# B312B.net
KiCad netlist of a schematic drawn in EAGLE
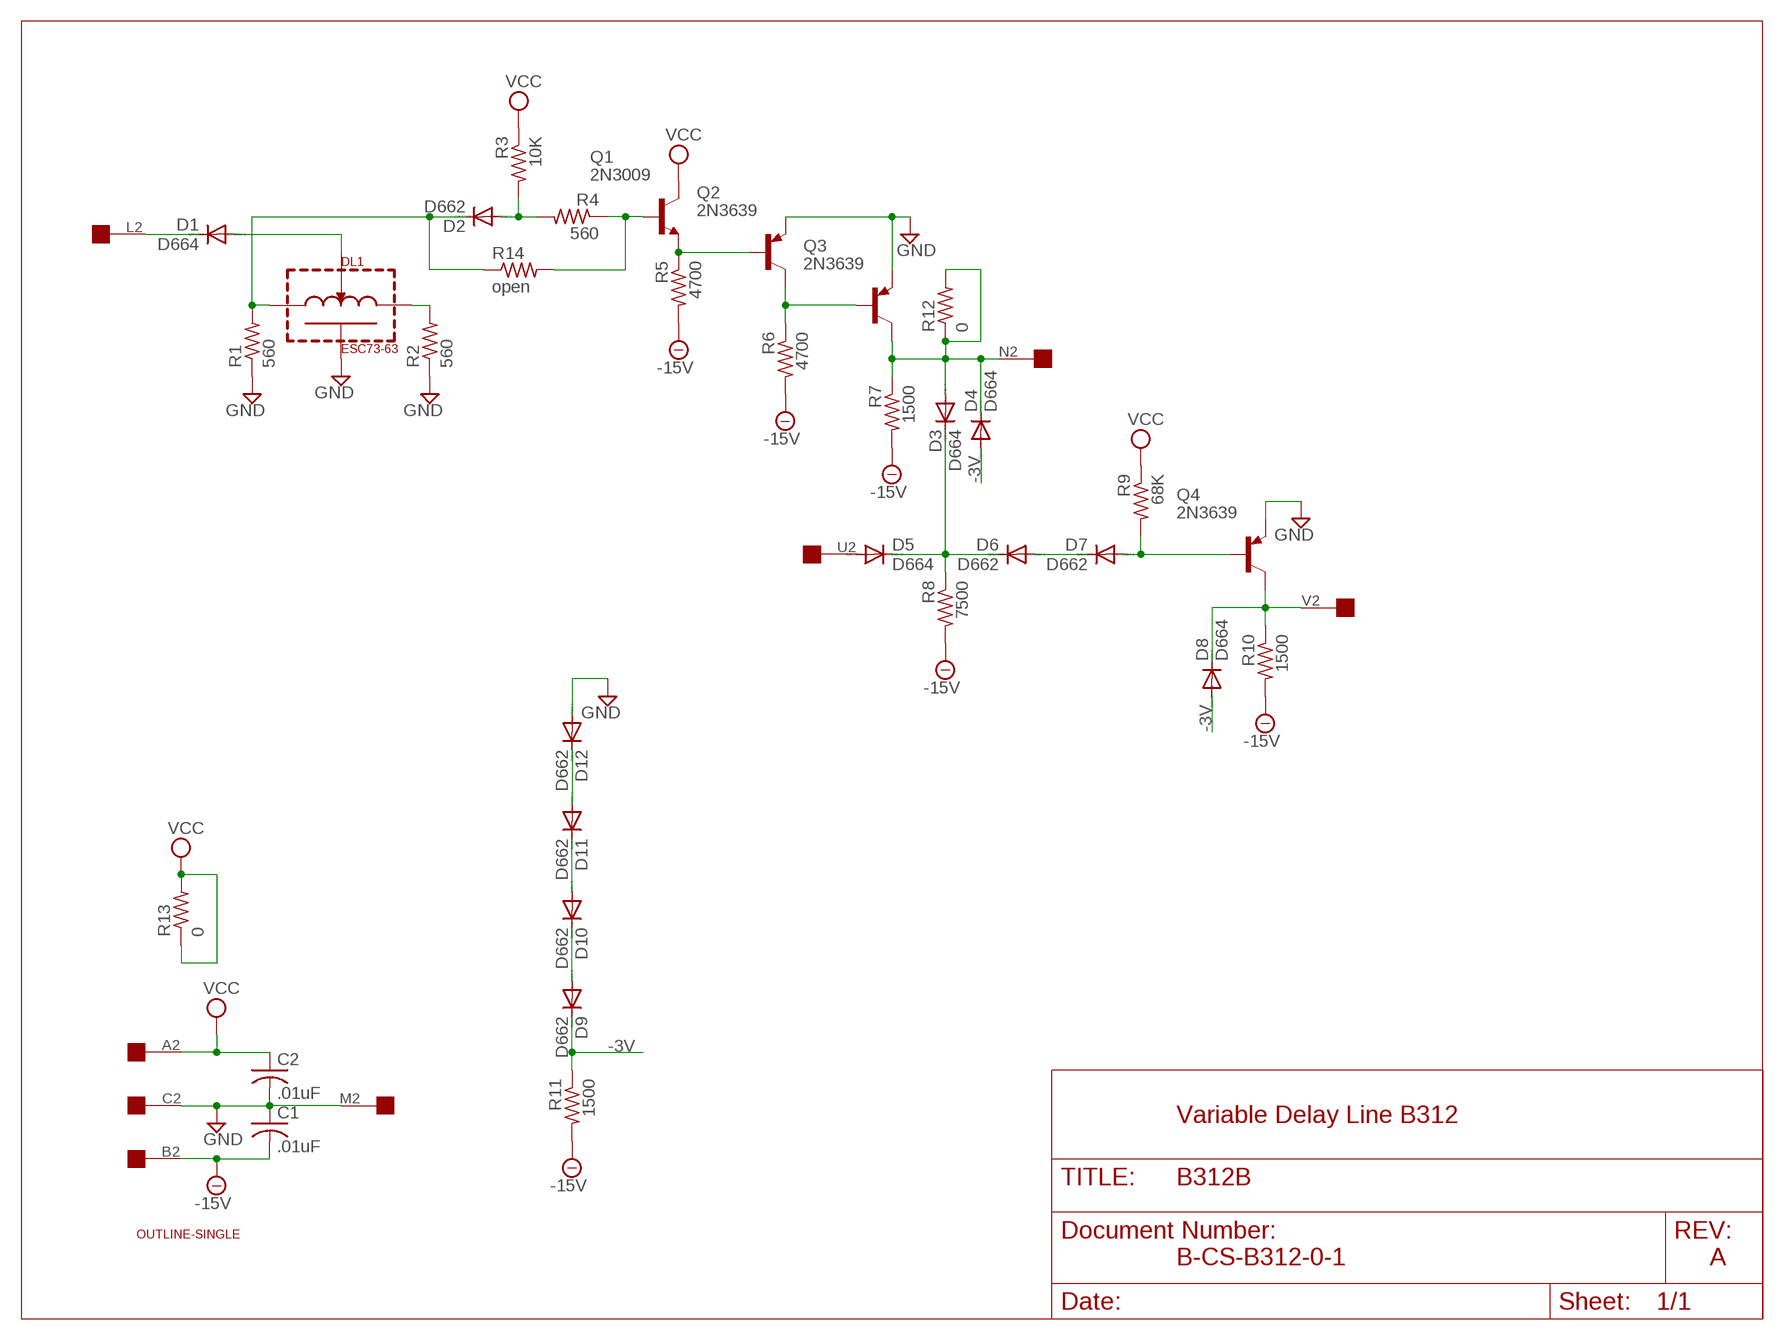
[diagram p0: schematic, sheet 1]

(export (version "E")
  (design (tool "Eeschema 10.0.6"))
  (components
    (comp (ref "C1")
      (value ".01uF")
      (footprint "eagle-import:C063-025X075")
      (libsource (lib "eagle-import") (part "C-US"))
    )
    (comp (ref "C2")
      (value ".01uF")
      (footprint "eagle-import:C063-025X075")
      (libsource (lib "eagle-import") (part "C-US"))
    )
    (comp (ref "D1")
      (value "D664")
      (footprint "eagle-import:DO35-10")
      (libsource (lib "eagle-import") (part "DIODE-DO35-10"))
    )
    (comp (ref "D2")
      (value "D662")
      (footprint "eagle-import:DO35-10")
      (libsource (lib "eagle-import") (part "DIODE-DO35-10"))
    )
    (comp (ref "D3")
      (value "D664")
      (footprint "eagle-import:DO35-10")
      (libsource (lib "eagle-import") (part "DIODE-DO35-10"))
    )
    (comp (ref "D4")
      (value "D664")
      (footprint "eagle-import:DO35-10")
      (libsource (lib "eagle-import") (part "DIODE-DO35-10"))
    )
    (comp (ref "D5")
      (value "D664")
      (footprint "eagle-import:DO35-10")
      (libsource (lib "eagle-import") (part "DIODE-DO35-10"))
    )
    (comp (ref "D6")
      (value "D662")
      (footprint "eagle-import:DO35-10")
      (libsource (lib "eagle-import") (part "DIODE-DO35-10"))
    )
    (comp (ref "D7")
      (value "D662")
      (footprint "eagle-import:DO35-10")
      (libsource (lib "eagle-import") (part "DIODE-DO35-10"))
    )
    (comp (ref "D8")
      (value "D664")
      (footprint "eagle-import:DO35-10")
      (libsource (lib "eagle-import") (part "DIODE-DO35-10"))
    )
    (comp (ref "D9")
      (value "D662")
      (footprint "eagle-import:DO35-10")
      (libsource (lib "eagle-import") (part "DIODE-DO35-10"))
    )
    (comp (ref "D10")
      (value "D662")
      (footprint "eagle-import:DO35-10")
      (libsource (lib "eagle-import") (part "DIODE-DO35-10"))
    )
    (comp (ref "D11")
      (value "D662")
      (footprint "eagle-import:DO35-10")
      (libsource (lib "eagle-import") (part "DIODE-DO35-10"))
    )
    (comp (ref "D12")
      (value "D662")
      (footprint "eagle-import:DO35-10")
      (libsource (lib "eagle-import") (part "DIODE-DO35-10"))
    )
    (comp (ref "DL1")
      (value "ESC73-63")
      (footprint "eagle-import:DELAYLINE")
      (libsource (lib "eagle-import") (part "DELAYLINE"))
    )
    (comp (ref "Q1")
      (value "2N3009")
      (footprint "eagle-import:TO5")
      (libsource (lib "eagle-import") (part "-NPN-TO5"))
    )
    (comp (ref "Q2")
      (value "2N3639")
      (footprint "eagle-import:TO5")
      (libsource (lib "eagle-import") (part "-PNP-TO5"))
    )
    (comp (ref "Q3")
      (value "2N3639")
      (footprint "eagle-import:TO5")
      (libsource (lib "eagle-import") (part "-PNP-TO5"))
    )
    (comp (ref "Q4")
      (value "2N3639")
      (footprint "eagle-import:TO5")
      (libsource (lib "eagle-import") (part "-PNP-TO5"))
    )
    (comp (ref "R1")
      (value "560")
      (footprint "eagle-import:0207_10")
      (libsource (lib "eagle-import") (part "R-US_0207/10"))
    )
    (comp (ref "R2")
      (value "560")
      (footprint "eagle-import:0207_10")
      (libsource (lib "eagle-import") (part "R-US_0207/10"))
    )
    (comp (ref "R3")
      (value "10K")
      (footprint "eagle-import:0207_10")
      (libsource (lib "eagle-import") (part "R-US_0207/10"))
    )
    (comp (ref "R4")
      (value "560")
      (footprint "eagle-import:0207_10")
      (libsource (lib "eagle-import") (part "R-US_0207/10"))
    )
    (comp (ref "R5")
      (value "4700")
      (footprint "eagle-import:0207_10")
      (libsource (lib "eagle-import") (part "R-US_0207/10"))
    )
    (comp (ref "R6")
      (value "4700")
      (footprint "eagle-import:0207_10")
      (libsource (lib "eagle-import") (part "R-US_0207/10"))
    )
    (comp (ref "R7")
      (value "1500")
      (footprint "eagle-import:0207_10")
      (libsource (lib "eagle-import") (part "R-US_0207/10"))
    )
    (comp (ref "R8")
      (value "7500")
      (footprint "eagle-import:0207_10")
      (libsource (lib "eagle-import") (part "R-US_0207/10"))
    )
    (comp (ref "R9")
      (value "68K")
      (footprint "eagle-import:0207_10")
      (libsource (lib "eagle-import") (part "R-US_0207/10"))
    )
    (comp (ref "R10")
      (value "1500")
      (footprint "eagle-import:0207_10")
      (libsource (lib "eagle-import") (part "R-US_0207/10"))
    )
    (comp (ref "R11")
      (value "1500")
      (footprint "eagle-import:0207_10")
      (libsource (lib "eagle-import") (part "R-US_0207/10"))
    )
    (comp (ref "R12")
      (value "0")
      (footprint "eagle-import:0207_10")
      (libsource (lib "eagle-import") (part "R-US_0207/10"))
    )
    (comp (ref "R13")
      (value "0")
      (footprint "eagle-import:0207_10")
      (libsource (lib "eagle-import") (part "R-US_0207/10"))
    )
    (comp (ref "R14")
      (value "open")
      (footprint "eagle-import:0207_10")
      (libsource (lib "eagle-import") (part "R-US_0207/10"))
    )
    (comp (ref "U$1")
      (value "OUTLINE-SINGLE")
      (footprint "eagle-import:SINGLE")
      (libsource (lib "eagle-import") (part "OUTLINE-SINGLE"))
    )
    (comp (ref "U$2")
      (value "EDGE-1")
      (footprint "eagle-import:EDGE-CON1")
      (libsource (lib "eagle-import") (part "EDGE-1"))
    )
  )
  (nets
    (net (code "1") (name "-15V") (class "Default")
      (node (ref "C1") (pin "2") (pinfunction "2_2") (pintype "passive"))
      (node (ref "R10") (pin "2") (pinfunction "2_2") (pintype "passive"))
      (node (ref "R11") (pin "2") (pinfunction "2_2") (pintype "passive"))
      (node (ref "R5") (pin "2") (pinfunction "2_2") (pintype "passive"))
      (node (ref "R6") (pin "2") (pinfunction "2_2") (pintype "passive"))
      (node (ref "R7") (pin "2") (pinfunction "2_2") (pintype "passive"))
      (node (ref "R8") (pin "2") (pinfunction "2_2") (pintype "passive"))
      (node (ref "U$2") (pin "B2") (pinfunction "1_B2") (pintype "bidirectional"))
    )
    (net (code "2") (name "/-3V") (class "Default")
      (node (ref "D4") (pin "A") (pinfunction "A_A") (pintype "passive"))
      (node (ref "D8") (pin "A") (pinfunction "A_A") (pintype "passive"))
      (node (ref "D9") (pin "C") (pinfunction "C_C") (pintype "passive"))
      (node (ref "R11") (pin "1") (pinfunction "1_1") (pintype "passive"))
    )
    (net (code "3") (name "GND") (class "Default")
      (node (ref "C1") (pin "1") (pinfunction "1_1") (pintype "passive"))
      (node (ref "C2") (pin "2") (pinfunction "2_2") (pintype "passive"))
      (node (ref "D12") (pin "A") (pinfunction "A_A") (pintype "passive"))
      (node (ref "DL1") (pin "G") (pinfunction "G_G") (pintype "passive"))
      (node (ref "Q2") (pin "1") (pinfunction "E_1") (pintype "passive"))
      (node (ref "Q3") (pin "1") (pinfunction "E_1") (pintype "passive"))
      (node (ref "Q4") (pin "1") (pinfunction "E_1") (pintype "passive"))
      (node (ref "R1") (pin "1") (pinfunction "1_1") (pintype "passive"))
      (node (ref "R2") (pin "1") (pinfunction "1_1") (pintype "passive"))
      (node (ref "U$2") (pin "C2") (pinfunction "1_C2") (pintype "bidirectional"))
      (node (ref "U$2") (pin "M2") (pinfunction "1_M2") (pintype "bidirectional"))
    )
    (net (code "4") (name "Net-(D1-PadA)") (class "Default")
      (node (ref "D1") (pin "A") (pinfunction "A_A") (pintype "passive"))
      (node (ref "DL1") (pin "V") (pinfunction "V_V") (pintype "passive"))
    )
    (net (code "5") (name "Net-(D2-PadA)") (class "Default")
      (node (ref "D2") (pin "A") (pinfunction "A_A") (pintype "passive"))
      (node (ref "R3") (pin "2") (pinfunction "2_2") (pintype "passive"))
      (node (ref "R4") (pin "2") (pinfunction "2_2") (pintype "passive"))
    )
    (net (code "6") (name "Net-(D2-PadC)") (class "Default")
      (node (ref "D2") (pin "C") (pinfunction "C_C") (pintype "passive"))
      (node (ref "DL1") (pin "L") (pinfunction "L_L") (pintype "passive"))
      (node (ref "R1") (pin "2") (pinfunction "2_2") (pintype "passive"))
      (node (ref "R14") (pin "1") (pinfunction "1_1") (pintype "passive"))
    )
    (net (code "7") (name "Net-(D3-PadC)") (class "Default")
      (node (ref "D3") (pin "C") (pinfunction "C_C") (pintype "passive"))
      (node (ref "D5") (pin "C") (pinfunction "C_C") (pintype "passive"))
      (node (ref "D6") (pin "C") (pinfunction "C_C") (pintype "passive"))
      (node (ref "R8") (pin "1") (pinfunction "1_1") (pintype "passive"))
    )
    (net (code "8") (name "Net-(D6-PadA)") (class "Default")
      (node (ref "D6") (pin "A") (pinfunction "A_A") (pintype "passive"))
      (node (ref "D7") (pin "C") (pinfunction "C_C") (pintype "passive"))
    )
    (net (code "9") (name "Net-(D10-PadA)") (class "Default")
      (node (ref "D10") (pin "A") (pinfunction "A_A") (pintype "passive"))
      (node (ref "D11") (pin "C") (pinfunction "C_C") (pintype "passive"))
    )
    (net (code "10") (name "Net-(D10-PadC)") (class "Default")
      (node (ref "D10") (pin "C") (pinfunction "C_C") (pintype "passive"))
      (node (ref "D9") (pin "A") (pinfunction "A_A") (pintype "passive"))
    )
    (net (code "11") (name "Net-(D11-PadA)") (class "Default")
      (node (ref "D11") (pin "A") (pinfunction "A_A") (pintype "passive"))
      (node (ref "D12") (pin "C") (pinfunction "C_C") (pintype "passive"))
    )
    (net (code "12") (name "Net-(DL1-PadR)") (class "Default")
      (node (ref "DL1") (pin "R") (pinfunction "R_R") (pintype "passive"))
      (node (ref "R2") (pin "2") (pinfunction "2_2") (pintype "passive"))
    )
    (net (code "13") (name "Net-(Q1-B)") (class "Default")
      (node (ref "Q1") (pin "2") (pinfunction "B_2") (pintype "passive"))
      (node (ref "R14") (pin "2") (pinfunction "2_2") (pintype "passive"))
      (node (ref "R4") (pin "1") (pinfunction "1_1") (pintype "passive"))
    )
    (net (code "14") (name "Net-(Q1-E)") (class "Default")
      (node (ref "Q1") (pin "1") (pinfunction "E_1") (pintype "passive"))
      (node (ref "Q2") (pin "2") (pinfunction "B_2") (pintype "passive"))
      (node (ref "R5") (pin "1") (pinfunction "1_1") (pintype "passive"))
    )
    (net (code "15") (name "Net-(Q2-C)") (class "Default")
      (node (ref "Q2") (pin "3") (pinfunction "C_3") (pintype "passive"))
      (node (ref "Q3") (pin "2") (pinfunction "B_2") (pintype "passive"))
      (node (ref "R6") (pin "1") (pinfunction "1_1") (pintype "passive"))
    )
    (net (code "16") (name "Net-(Q3-C)") (class "Default")
      (node (ref "D3") (pin "A") (pinfunction "A_A") (pintype "passive"))
      (node (ref "D4") (pin "C") (pinfunction "C_C") (pintype "passive"))
      (node (ref "Q3") (pin "3") (pinfunction "C_3") (pintype "passive"))
      (node (ref "R12") (pin "1") (pinfunction "1_1") (pintype "passive"))
      (node (ref "R12") (pin "2") (pinfunction "2_2") (pintype "passive"))
      (node (ref "R7") (pin "1") (pinfunction "1_1") (pintype "passive"))
      (node (ref "U$2") (pin "N2") (pinfunction "1_N2") (pintype "bidirectional"))
    )
    (net (code "17") (name "Net-(Q4-B)") (class "Default")
      (node (ref "D7") (pin "A") (pinfunction "A_A") (pintype "passive"))
      (node (ref "Q4") (pin "2") (pinfunction "B_2") (pintype "passive"))
      (node (ref "R9") (pin "2") (pinfunction "2_2") (pintype "passive"))
    )
    (net (code "18") (name "Net-(Q4-C)") (class "Default")
      (node (ref "D8") (pin "C") (pinfunction "C_C") (pintype "passive"))
      (node (ref "Q4") (pin "3") (pinfunction "C_3") (pintype "passive"))
      (node (ref "R10") (pin "1") (pinfunction "1_1") (pintype "passive"))
      (node (ref "U$2") (pin "V2") (pinfunction "1_V2") (pintype "bidirectional"))
    )
    (net (code "19") (name "Net-(U$2J-1)") (class "Default")
      (node (ref "D1") (pin "C") (pinfunction "C_C") (pintype "passive"))
      (node (ref "U$2") (pin "L2") (pinfunction "1_L2") (pintype "bidirectional"))
    )
    (net (code "20") (name "Net-(U$2Q-1)") (class "Default")
      (node (ref "D5") (pin "A") (pinfunction "A_A") (pintype "passive"))
      (node (ref "U$2") (pin "U2") (pinfunction "1_U2") (pintype "bidirectional"))
    )
    (net (code "21") (name "VCC") (class "Default")
      (node (ref "C2") (pin "1") (pinfunction "1_1") (pintype "passive"))
      (node (ref "Q1") (pin "3") (pinfunction "C_3") (pintype "passive"))
      (node (ref "R13") (pin "1") (pinfunction "1_1") (pintype "passive"))
      (node (ref "R13") (pin "2") (pinfunction "2_2") (pintype "passive"))
      (node (ref "R3") (pin "1") (pinfunction "1_1") (pintype "passive"))
      (node (ref "R9") (pin "1") (pinfunction "1_1") (pintype "passive"))
      (node (ref "U$2") (pin "A2") (pinfunction "1_A2") (pintype "bidirectional"))
    )
  )
)
